# Sheet1.net
KiCad netlist of a schematic drawn in Altium Designer
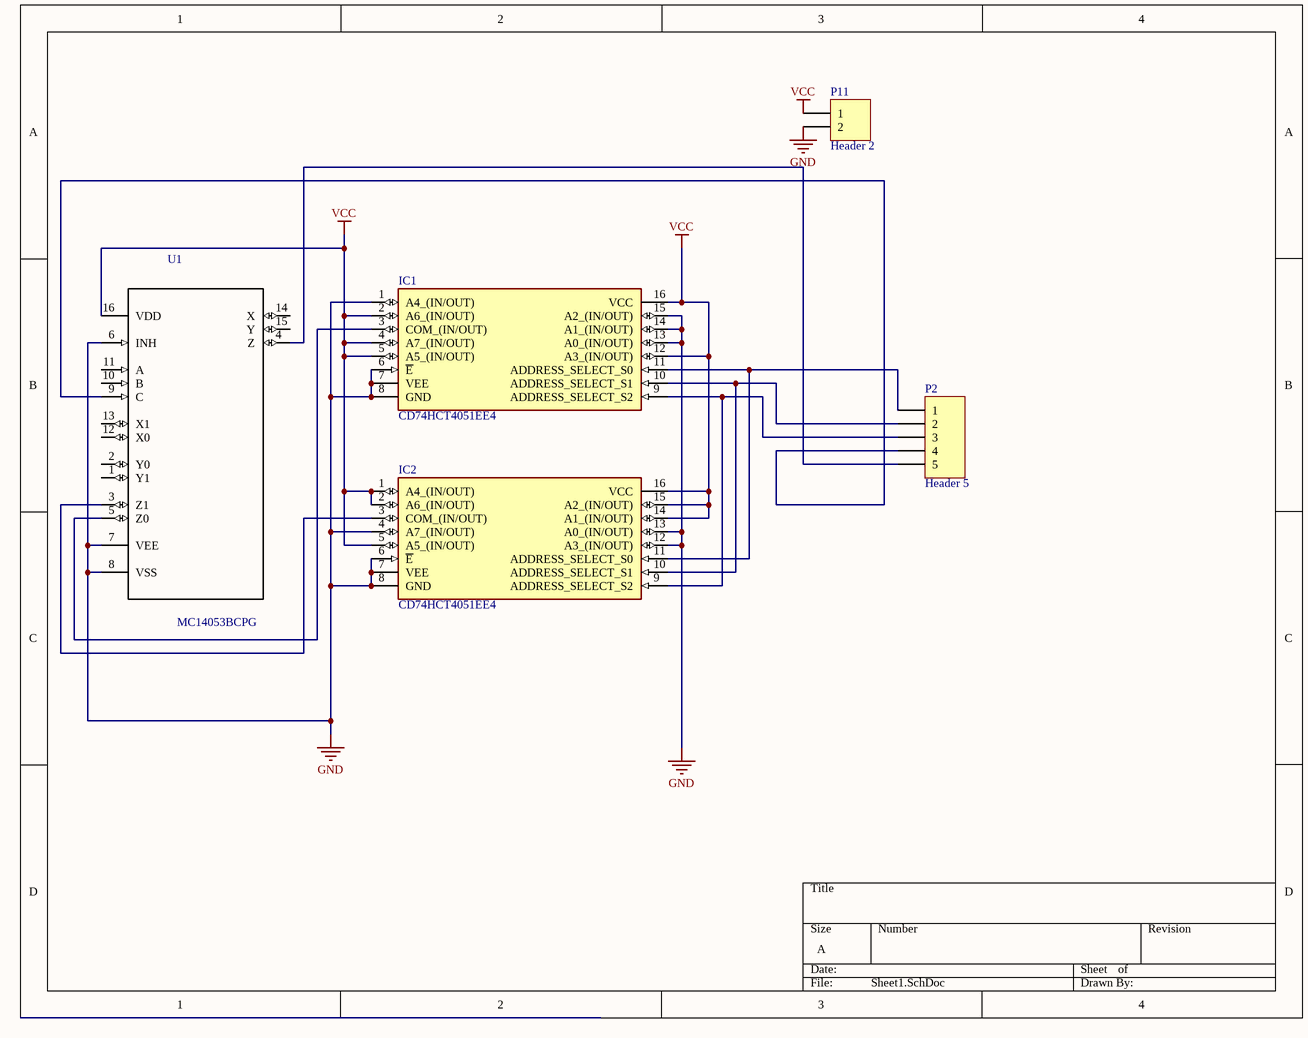
[diagram p0: Sheet1.SchDoc]

(export (version "E")
  (design (tool "Eeschema 10.0.6"))
  (components
    (comp (ref "IC1")
      (value "CD74HCT4051EE4")
      (footprint "SamacSys:DIP794W53P254L1930H508Q16N")
      (description "Integrated Circuit")
      (fields (field (name "MOUSER PART NUMBER") "595-CD74HCT4051EE4"))
      (libsource (lib "744051") (part "CD74HCT4051EE4"))
    )
    (comp (ref "IC2")
      (value "CD74HCT4051EE4")
      (footprint "SamacSys:DIP794W53P254L1930H508Q16N")
      (description "Integrated Circuit")
      (fields (field (name "MOUSER PART NUMBER") "595-CD74HCT4051EE4"))
      (libsource (lib "744051") (part "CD74HCT4051EE4"))
    )
    (comp (ref "P2")
      (value "Header 5")
      (footprint "HDR1X5")
      (description "Header, 5-Pin")
      (fields (field (name "PUBLISHER") "Altium Limited"))
      (libsource (lib "Miscellaneous Connectors") (part "Header 5"))
    )
    (comp (ref "P11")
      (value "Header 2")
      (footprint "HDR1X2")
      (description "Header, 2-Pin")
      (fields (field (name "PUBLISHER") "Altium Limited"))
      (libsource (lib "Miscellaneous Connectors") (part "Header 2"))
    )
    (comp (ref "U1")
      (value "MC14053BCPG")
      (footprint "*DIP254P762X444-16")
      (description "Ic Mux/Demux Triple 2x1 16dip - Mc14053bcpg")
      (fields (field (name "MF") "ON Semiconductor"))
      (libsource (lib "MC14053BCPG") (part "MC14053BCPG"))
    )
  )
  (nets
    (net (code "1") (name "GND") (class "Default")
      (node (ref "IC1") (pin "1") (pinfunction "A4_(IN/OUT)_1") (pintype "bidirectional"))
      (node (ref "IC1") (pin "13") (pinfunction "A0_(IN/OUT)_13") (pintype "bidirectional"))
      (node (ref "IC1") (pin "14") (pinfunction "A1_(IN/OUT)_14") (pintype "bidirectional"))
      (node (ref "IC1") (pin "15") (pinfunction "A2_(IN/OUT)_15") (pintype "bidirectional"))
      (node (ref "IC1") (pin "6") (pinfunction "~{E}_6") (pintype "input"))
      (node (ref "IC1") (pin "7") (pinfunction "VEE_7") (pintype "power_in"))
      (node (ref "IC1") (pin "8") (pinfunction "GND_8") (pintype "power_in"))
      (node (ref "IC2") (pin "12") (pinfunction "A3_(IN/OUT)_12") (pintype "bidirectional"))
      (node (ref "IC2") (pin "13") (pinfunction "A0_(IN/OUT)_13") (pintype "bidirectional"))
      (node (ref "IC2") (pin "4") (pinfunction "A7_(IN/OUT)_4") (pintype "bidirectional"))
      (node (ref "IC2") (pin "6") (pinfunction "~{E}_6") (pintype "input"))
      (node (ref "IC2") (pin "7") (pinfunction "VEE_7") (pintype "power_in"))
      (node (ref "IC2") (pin "8") (pinfunction "GND_8") (pintype "power_in"))
      (node (ref "P11") (pin "2") (pinfunction "2_2") (pintype "passive"))
      (node (ref "U1") (pin "6") (pinfunction "INH_6") (pintype "input"))
      (node (ref "U1") (pin "7") (pinfunction "VEE_7") (pintype "power_in"))
      (node (ref "U1") (pin "8") (pinfunction "VSS_8") (pintype "power_in"))
    )
    (net (code "2") (name "Net-(IC1-ADDRESS_SELECT_S0)") (class "Default")
      (node (ref "IC1") (pin "11") (pinfunction "ADDRESS_SELECT_S0_11") (pintype "input"))
      (node (ref "IC2") (pin "11") (pinfunction "ADDRESS_SELECT_S0_11") (pintype "input"))
      (node (ref "P2") (pin "1") (pinfunction "1_1") (pintype "passive"))
    )
    (net (code "3") (name "Net-(IC1-ADDRESS_SELECT_S1)") (class "Default")
      (node (ref "IC1") (pin "10") (pinfunction "ADDRESS_SELECT_S1_10") (pintype "input"))
      (node (ref "IC2") (pin "10") (pinfunction "ADDRESS_SELECT_S1_10") (pintype "input"))
      (node (ref "P2") (pin "2") (pinfunction "2_2") (pintype "passive"))
    )
    (net (code "4") (name "Net-(IC1-ADDRESS_SELECT_S2)") (class "Default")
      (node (ref "IC1") (pin "9") (pinfunction "ADDRESS_SELECT_S2_9") (pintype "input"))
      (node (ref "IC2") (pin "9") (pinfunction "ADDRESS_SELECT_S2_9") (pintype "input"))
      (node (ref "P2") (pin "3") (pinfunction "3_3") (pintype "passive"))
    )
    (net (code "5") (name "Net-(IC1-COM_(IN{slash}OUT))") (class "Default")
      (node (ref "IC1") (pin "3") (pinfunction "COM_(IN/OUT)_3") (pintype "bidirectional"))
      (node (ref "U1") (pin "5") (pinfunction "Z0_5") (pintype "bidirectional"))
    )
    (net (code "6") (name "Net-(IC2-COM_(IN{slash}OUT))") (class "Default")
      (node (ref "IC2") (pin "3") (pinfunction "COM_(IN/OUT)_3") (pintype "bidirectional"))
      (node (ref "U1") (pin "3") (pinfunction "Z1_3") (pintype "bidirectional"))
    )
    (net (code "7") (name "Net-(U1-C)") (class "Default")
      (node (ref "P2") (pin "4") (pinfunction "4_4") (pintype "passive"))
      (node (ref "U1") (pin "9") (pinfunction "C_9") (pintype "input"))
    )
    (net (code "8") (name "Net-(U1-Z)") (class "Default")
      (node (ref "P2") (pin "5") (pinfunction "5_5") (pintype "passive"))
      (node (ref "U1") (pin "4") (pinfunction "Z_4") (pintype "bidirectional"))
    )
    (net (code "9") (name "VCC") (class "Default")
      (node (ref "IC1") (pin "12") (pinfunction "A3_(IN/OUT)_12") (pintype "bidirectional"))
      (node (ref "IC1") (pin "16") (pinfunction "VCC_16") (pintype "power_in"))
      (node (ref "IC1") (pin "2") (pinfunction "A6_(IN/OUT)_2") (pintype "bidirectional"))
      (node (ref "IC1") (pin "4") (pinfunction "A7_(IN/OUT)_4") (pintype "bidirectional"))
      (node (ref "IC1") (pin "5") (pinfunction "A5_(IN/OUT)_5") (pintype "bidirectional"))
      (node (ref "IC2") (pin "1") (pinfunction "A4_(IN/OUT)_1") (pintype "bidirectional"))
      (node (ref "IC2") (pin "14") (pinfunction "A1_(IN/OUT)_14") (pintype "bidirectional"))
      (node (ref "IC2") (pin "15") (pinfunction "A2_(IN/OUT)_15") (pintype "bidirectional"))
      (node (ref "IC2") (pin "16") (pinfunction "VCC_16") (pintype "power_in"))
      (node (ref "IC2") (pin "2") (pinfunction "A6_(IN/OUT)_2") (pintype "bidirectional"))
      (node (ref "IC2") (pin "5") (pinfunction "A5_(IN/OUT)_5") (pintype "bidirectional"))
      (node (ref "P11") (pin "1") (pinfunction "1_1") (pintype "passive"))
      (node (ref "U1") (pin "16") (pinfunction "VDD_16") (pintype "power_in"))
    )
    (net (code "10") (name "unconnected-(U1-A-Pad11)") (class "Default")
      (node (ref "U1") (pin "11") (pinfunction "A_11") (pintype "input"))
    )
    (net (code "11") (name "unconnected-(U1-B-Pad10)") (class "Default")
      (node (ref "U1") (pin "10") (pinfunction "B_10") (pintype "input"))
    )
    (net (code "12") (name "unconnected-(U1-X-Pad14)") (class "Default")
      (node (ref "U1") (pin "14") (pinfunction "X_14") (pintype "bidirectional"))
    )
    (net (code "13") (name "unconnected-(U1-X0-Pad12)") (class "Default")
      (node (ref "U1") (pin "12") (pinfunction "X0_12") (pintype "bidirectional"))
    )
    (net (code "14") (name "unconnected-(U1-X1-Pad13)") (class "Default")
      (node (ref "U1") (pin "13") (pinfunction "X1_13") (pintype "bidirectional"))
    )
    (net (code "15") (name "unconnected-(U1-Y-Pad15)") (class "Default")
      (node (ref "U1") (pin "15") (pinfunction "Y_15") (pintype "bidirectional"))
    )
    (net (code "16") (name "unconnected-(U1-Y0-Pad2)") (class "Default")
      (node (ref "U1") (pin "2") (pinfunction "Y0_2") (pintype "bidirectional"))
    )
    (net (code "17") (name "unconnected-(U1-Y1-Pad1)") (class "Default")
      (node (ref "U1") (pin "1") (pinfunction "Y1_1") (pintype "bidirectional"))
    )
  )
)
